# tht-fet-board.net
KiCad netlist of a schematic drawn in EAGLE
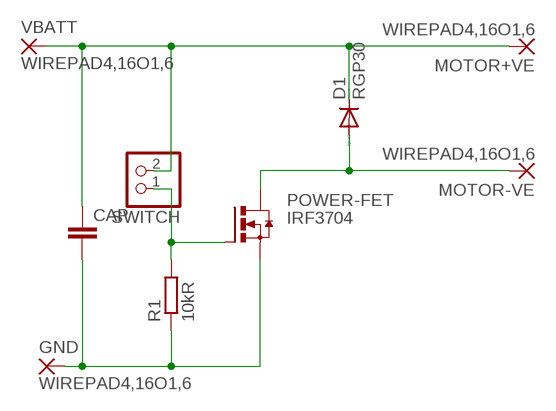
[diagram p0: schematic, sheet 1]

(export (version "E")
  (design (tool "Eeschema 10.0.6"))
  (components
    (comp (ref "CAP")
      (value "C-EU025-024X044")
      (footprint "eagle-import:C025-024X044")
      (libsource (lib "eagle-import") (part "C-EU025-024X044"))
    )
    (comp (ref "D1")
      (value "RGP30")
      (footprint "eagle-import:DO201-15")
      (libsource (lib "eagle-import") (part "RGP30"))
    )
    (comp (ref "GND")
      (value "WIREPAD4,16O1,6")
      (footprint "eagle-import:4,16O1,6")
      (libsource (lib "eagle-import") (part "WIREPAD4,16O1,6"))
    )
    (comp (ref "MOTOR+VE")
      (value "WIREPAD4,16O1,6")
      (footprint "eagle-import:4,16O1,6")
      (libsource (lib "eagle-import") (part "WIREPAD4,16O1,6"))
    )
    (comp (ref "MOTOR-VE")
      (value "WIREPAD4,16O1,6")
      (footprint "eagle-import:4,16O1,6")
      (libsource (lib "eagle-import") (part "WIREPAD4,16O1,6"))
    )
    (comp (ref "POWER-FET")
      (value "IRF3704")
      (footprint "eagle-import:TO220AH")
      (libsource (lib "eagle-import") (part "IRF3704"))
    )
    (comp (ref "R1")
      (value "10kR")
      (footprint "eagle-import:0207_15")
      (libsource (lib "eagle-import") (part "R-EU_0207/15"))
    )
    (comp (ref "SWITCH")
      (value "PINHD-1X2")
      (footprint "eagle-import:1X02")
      (libsource (lib "eagle-import") (part "PINHD-1X2"))
    )
    (comp (ref "VBATT")
      (value "WIREPAD4,16O1,6")
      (footprint "eagle-import:4,16O1,6")
      (libsource (lib "eagle-import") (part "WIREPAD4,16O1,6"))
    )
  )
  (nets
    (net (code "1") (name "Net-(GND-P)") (class "Default")
      (node (ref "CAP") (pin "2") (pinfunction "2_2") (pintype "passive"))
      (node (ref "GND") (pin "1") (pinfunction "P_1") (pintype "passive"))
      (node (ref "POWER-FET") (pin "E") (pinfunction "S_E") (pintype "passive"))
      (node (ref "R1") (pin "1") (pinfunction "1_1") (pintype "passive"))
    )
    (net (code "2") (name "Net-(MOTOR+VE-P)") (class "Default")
      (node (ref "CAP") (pin "1") (pinfunction "1_1") (pintype "passive"))
      (node (ref "D1") (pin "C") (pinfunction "C_C") (pintype "passive"))
      (node (ref "MOTOR+VE") (pin "1") (pinfunction "P_1") (pintype "passive"))
      (node (ref "SWITCH") (pin "2") (pinfunction "2_2") (pintype "passive"))
      (node (ref "VBATT") (pin "1") (pinfunction "P_1") (pintype "passive"))
    )
    (net (code "3") (name "Net-(MOTOR-VE-P)") (class "Default")
      (node (ref "D1") (pin "A") (pinfunction "A_A") (pintype "passive"))
      (node (ref "MOTOR-VE") (pin "1") (pinfunction "P_1") (pintype "passive"))
      (node (ref "POWER-FET") (pin "C") (pinfunction "D_C") (pintype "passive"))
    )
    (net (code "4") (name "Net-(POWER-FET-G)") (class "Default")
      (node (ref "POWER-FET") (pin "B") (pinfunction "G_B") (pintype "passive"))
      (node (ref "R1") (pin "2") (pinfunction "2_2") (pintype "passive"))
      (node (ref "SWITCH") (pin "1") (pinfunction "1_1") (pintype "passive"))
    )
  )
)
